# ARM_POWER.net
KiCad netlist of a schematic drawn in Altium Designer
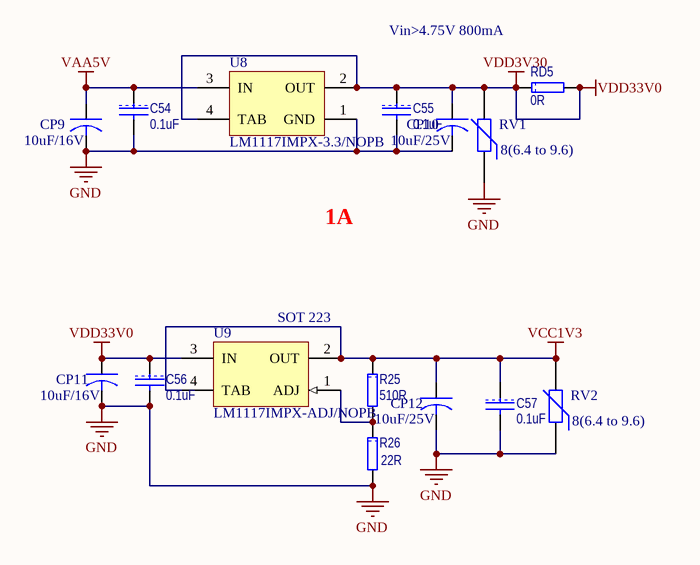
[diagram p0: ARM POWER.SchDoc]

(export (version "E")
  (design (tool "Eeschema 10.0.6"))
  (components
    (comp (ref "C54")
      (value "0.1uF")
      (footprint "1608[0603]")
      (description "Capacitor")
      (fields (field (name "MANUFACTURER") "TDK"))
      (libsource (lib "*") (part "CAP"))
    )
    (comp (ref "C55")
      (value "0.1uF")
      (footprint "1608[0603]")
      (description "Capacitor")
      (fields (field (name "MANUFACTURER") "TDK"))
      (libsource (lib "*") (part "CAP"))
    )
    (comp (ref "C56")
      (value "0.1uF")
      (footprint "1608[0603]")
      (description "Capacitor")
      (fields (field (name "MANUFACTURER") "TDK"))
      (libsource (lib "*") (part "CAP"))
    )
    (comp (ref "C57")
      (value "0.1uF")
      (footprint "1608[0603]")
      (description "Capacitor")
      (fields (field (name "MANUFACTURER") "TDK"))
      (libsource (lib "*") (part "CAP"))
    )
    (comp (ref "CP9")
      (value "10uF/16V")
      (footprint "3216[1206]")
      (description "Tantalum Capacitor")
      (libsource (lib "*") (part "CAPACITOR"))
    )
    (comp (ref "CP10")
      (value "10uF/25V")
      (footprint "6032[2312]CC")
      (description "Tantalum Capacitor")
      (libsource (lib "*") (part "CAPACITOR"))
    )
    (comp (ref "CP11")
      (value "10uF/16V")
      (footprint "3216[1206]")
      (description "Tantalum Capacitor")
      (libsource (lib "*") (part "CAPACITOR"))
    )
    (comp (ref "CP12")
      (value "10uF/25V")
      (footprint "6032[2312]CC")
      (description "Tantalum Capacitor")
      (libsource (lib "*") (part "CAPACITOR"))
    )
    (comp (ref "R25")
      (value "510R")
      (footprint "1608[0603]R")
      (description "RES")
      (fields (field (name "MANUFACTURER") "vishay"))
      (libsource (lib "*") (part "RES"))
    )
    (comp (ref "R26")
      (value "22R")
      (footprint "1608[0603]R")
      (description "RES")
      (fields (field (name "MANUFACTURER") "vishay"))
      (libsource (lib "*") (part "RES"))
    )
    (comp (ref "RD5")
      (value "0R")
      (description "RES")
      (fields (field (name "MANUFACTURER") "vishay"))
      (libsource (lib "*") (part "RES"))
    )
    (comp (ref "RV1")
      (value "8(6.4 to 9.6)")
      (footprint "1608[0603]RV")
      (description "压敏电阻")
      (fields (field (name "PUBLISHER") "Altium Limited"))
      (libsource (lib "Miscellaneous Devices") (part "Res Varistor"))
    )
    (comp (ref "RV2")
      (value "8(6.4 to 9.6)")
      (footprint "1608[0603]RV")
      (description "压敏电阻")
      (fields (field (name "PUBLISHER") "Altium Limited"))
      (libsource (lib "Miscellaneous Devices") (part "Res Varistor"))
    )
    (comp (ref "U8")
      (value "LM1117IMPX-3.3/NOPB")
      (footprint "MP04A_N")
      (description "800mA Low-Dropout Linear Regulator, 4-pin SOT-223, Pb-Free")
      (fields
        (field (name "PARTNUMBER") "LM1117MPX-3.3/NOPB")
        (field (name "MANUFACTURER") "National Semiconductor")
        (field (name "PUBLISHER") "Altium Limited")
      )
      (libsource (lib "NSC LDO") (part "LM1117MPX-3.3/NOPB"))
    )
    (comp (ref "U9")
      (value "LM1117IMPX-ADJ/NOPB")
      (footprint "MP04A_N")
      (description "800mA Low-Dropout Linear Regulator, 4-pin SOT-223, Pb-Free")
      (fields
        (field (name "PARTNUMBER") "LM1117MPX-ADJ/NOPB")
        (field (name "MANUFACTURER") "National Semiconductor")
        (field (name "PUBLISHER") "Altium Limited")
      )
      (libsource (lib "NSC LDO") (part "LM1117MPX-ADJ/NOPB"))
    )
  )
  (nets
    (net (code "1") (name "GND") (class "Default")
      (node (ref "C54") (pin "2") (pinfunction "2_2") (pintype "passive"))
      (node (ref "C55") (pin "2") (pinfunction "2_2") (pintype "passive"))
      (node (ref "C56") (pin "2") (pinfunction "2_2") (pintype "passive"))
      (node (ref "C57") (pin "2") (pinfunction "2_2") (pintype "passive"))
      (node (ref "CP10") (pin "2") (pinfunction "2_2") (pintype "passive"))
      (node (ref "CP11") (pin "2") (pinfunction "2_2") (pintype "passive"))
      (node (ref "CP12") (pin "2") (pinfunction "2_2") (pintype "passive"))
      (node (ref "CP9") (pin "2") (pinfunction "2_2") (pintype "passive"))
      (node (ref "R26") (pin "2") (pinfunction "2_2") (pintype "passive"))
      (node (ref "RV1") (pin "1") (pinfunction "1_1") (pintype "passive"))
      (node (ref "RV2") (pin "1") (pinfunction "1_1") (pintype "passive"))
      (node (ref "U8") (pin "1") (pinfunction "GND_1") (pintype "power_in"))
    )
    (net (code "2") (name "Net-(U9-ADJ)") (class "Default")
      (node (ref "R25") (pin "2") (pinfunction "2_2") (pintype "passive"))
      (node (ref "R26") (pin "1") (pinfunction "1_1") (pintype "passive"))
      (node (ref "U9") (pin "1") (pinfunction "ADJ_1") (pintype "input"))
    )
    (net (code "3") (name "VAA5V") (class "Default")
      (node (ref "C54") (pin "1") (pinfunction "1_1") (pintype "passive"))
      (node (ref "CP9") (pin "1") (pinfunction "1_1") (pintype "passive"))
      (node (ref "U8") (pin "3") (pinfunction "IN_3") (pintype "power_in"))
    )
    (net (code "4") (name "VCC1V3") (class "Default")
      (node (ref "C57") (pin "1") (pinfunction "1_1") (pintype "passive"))
      (node (ref "CP12") (pin "1") (pinfunction "1_1") (pintype "passive"))
      (node (ref "R25") (pin "1") (pinfunction "1_1") (pintype "passive"))
      (node (ref "RV2") (pin "2") (pinfunction "2_2") (pintype "passive"))
      (node (ref "U9") (pin "2") (pinfunction "OUT_2") (pintype "power_in"))
      (node (ref "U9") (pin "4") (pinfunction "TAB_4") (pintype "power_in"))
    )
    (net (code "5") (name "VDD33V0") (class "Default")
      (node (ref "C55") (pin "1") (pinfunction "1_1") (pintype "passive"))
      (node (ref "C56") (pin "1") (pinfunction "1_1") (pintype "passive"))
      (node (ref "CP10") (pin "1") (pinfunction "1_1") (pintype "passive"))
      (node (ref "CP11") (pin "1") (pinfunction "1_1") (pintype "passive"))
      (node (ref "RD5") (pin "1") (pinfunction "1_1") (pintype "passive"))
      (node (ref "RD5") (pin "2") (pinfunction "2_2") (pintype "passive"))
      (node (ref "RV1") (pin "2") (pinfunction "2_2") (pintype "passive"))
      (node (ref "U8") (pin "2") (pinfunction "OUT_2") (pintype "power_in"))
      (node (ref "U8") (pin "4") (pinfunction "TAB_4") (pintype "power_in"))
      (node (ref "U9") (pin "3") (pinfunction "IN_3") (pintype "power_in"))
    )
  )
)
